# v1.net
KiCad netlist of a schematic drawn in EAGLE
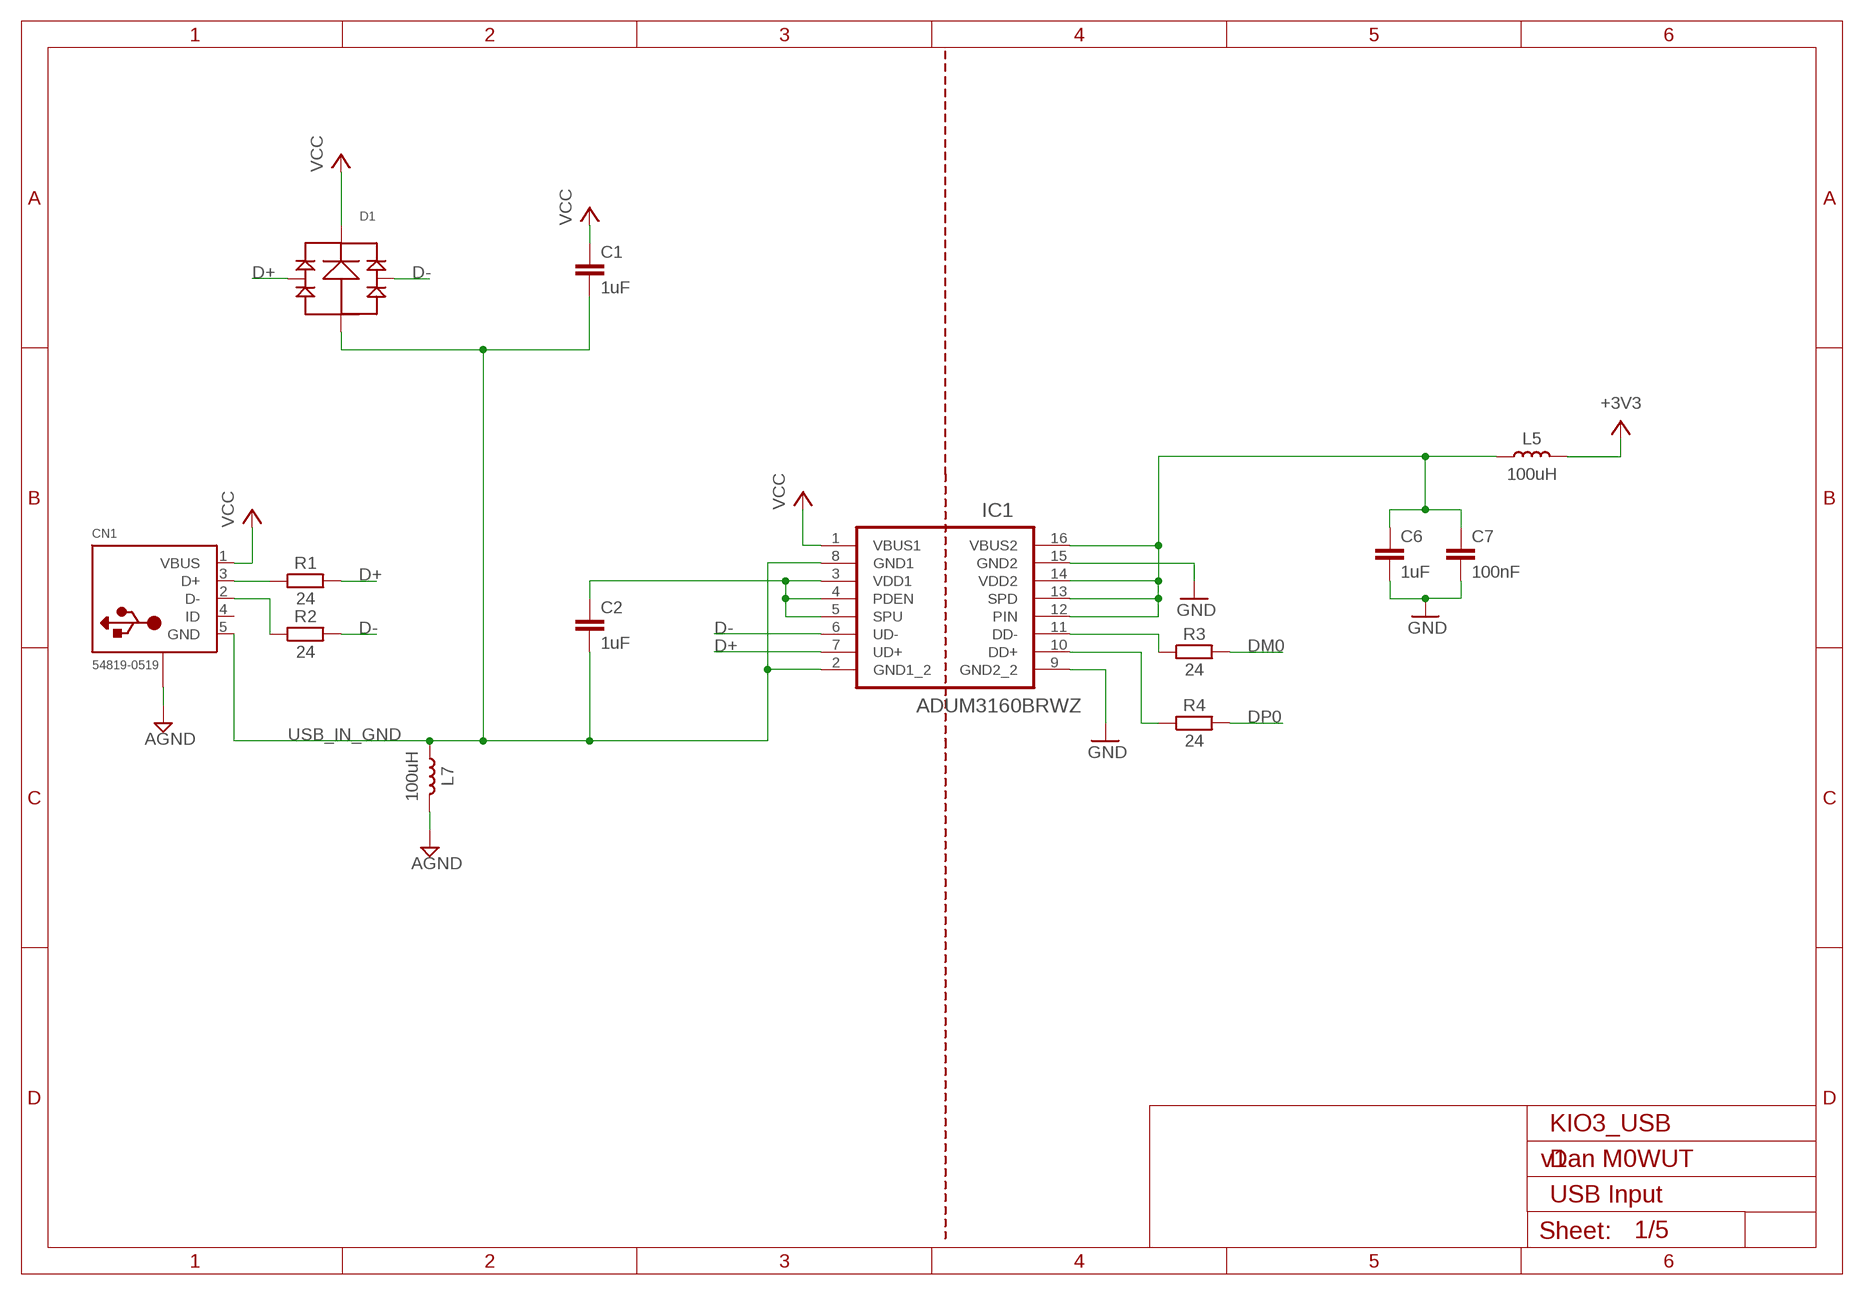
[diagram p0: schematic, sheet 1]
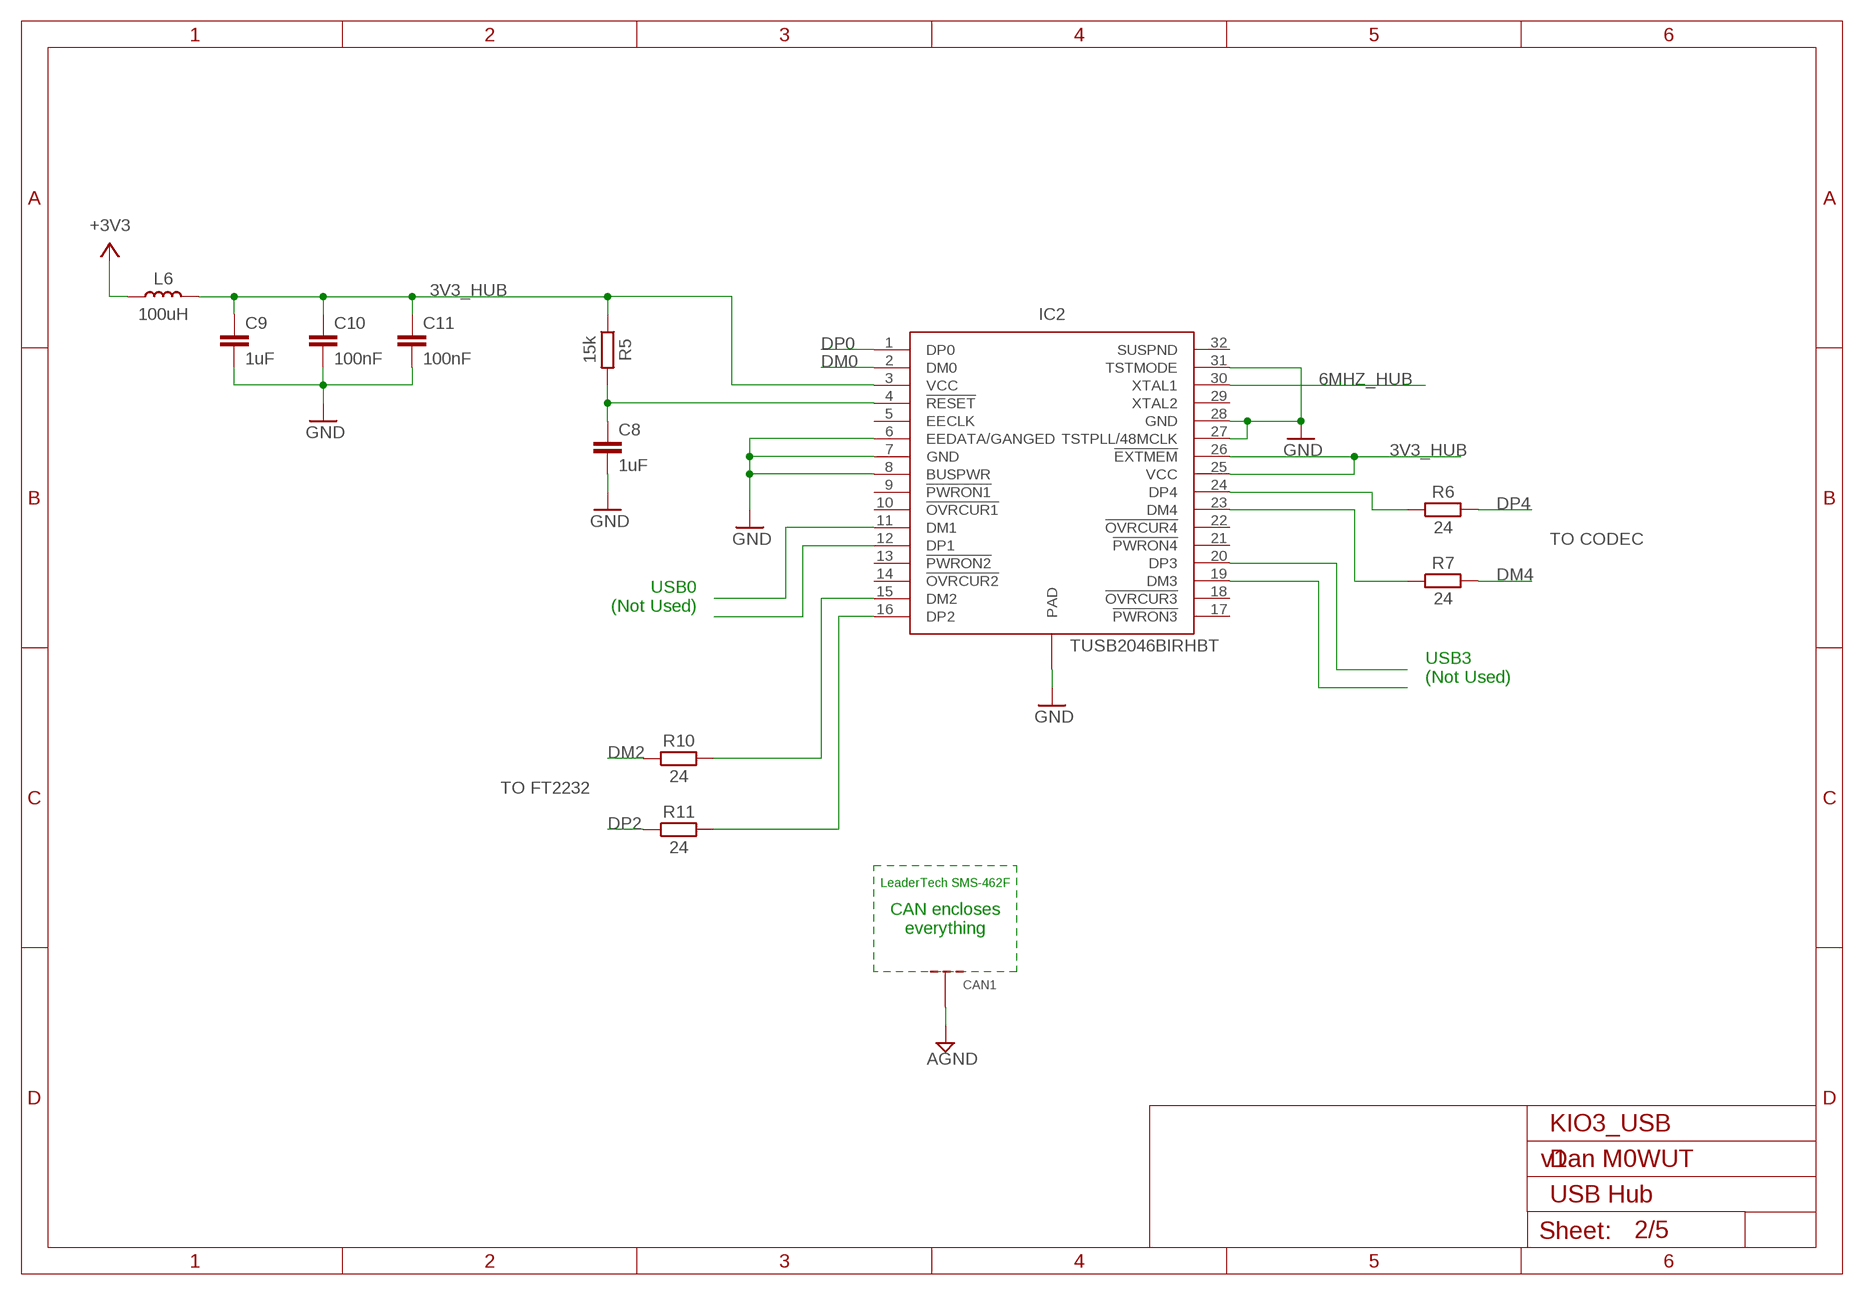
[diagram p1: schematic, sheet 2]
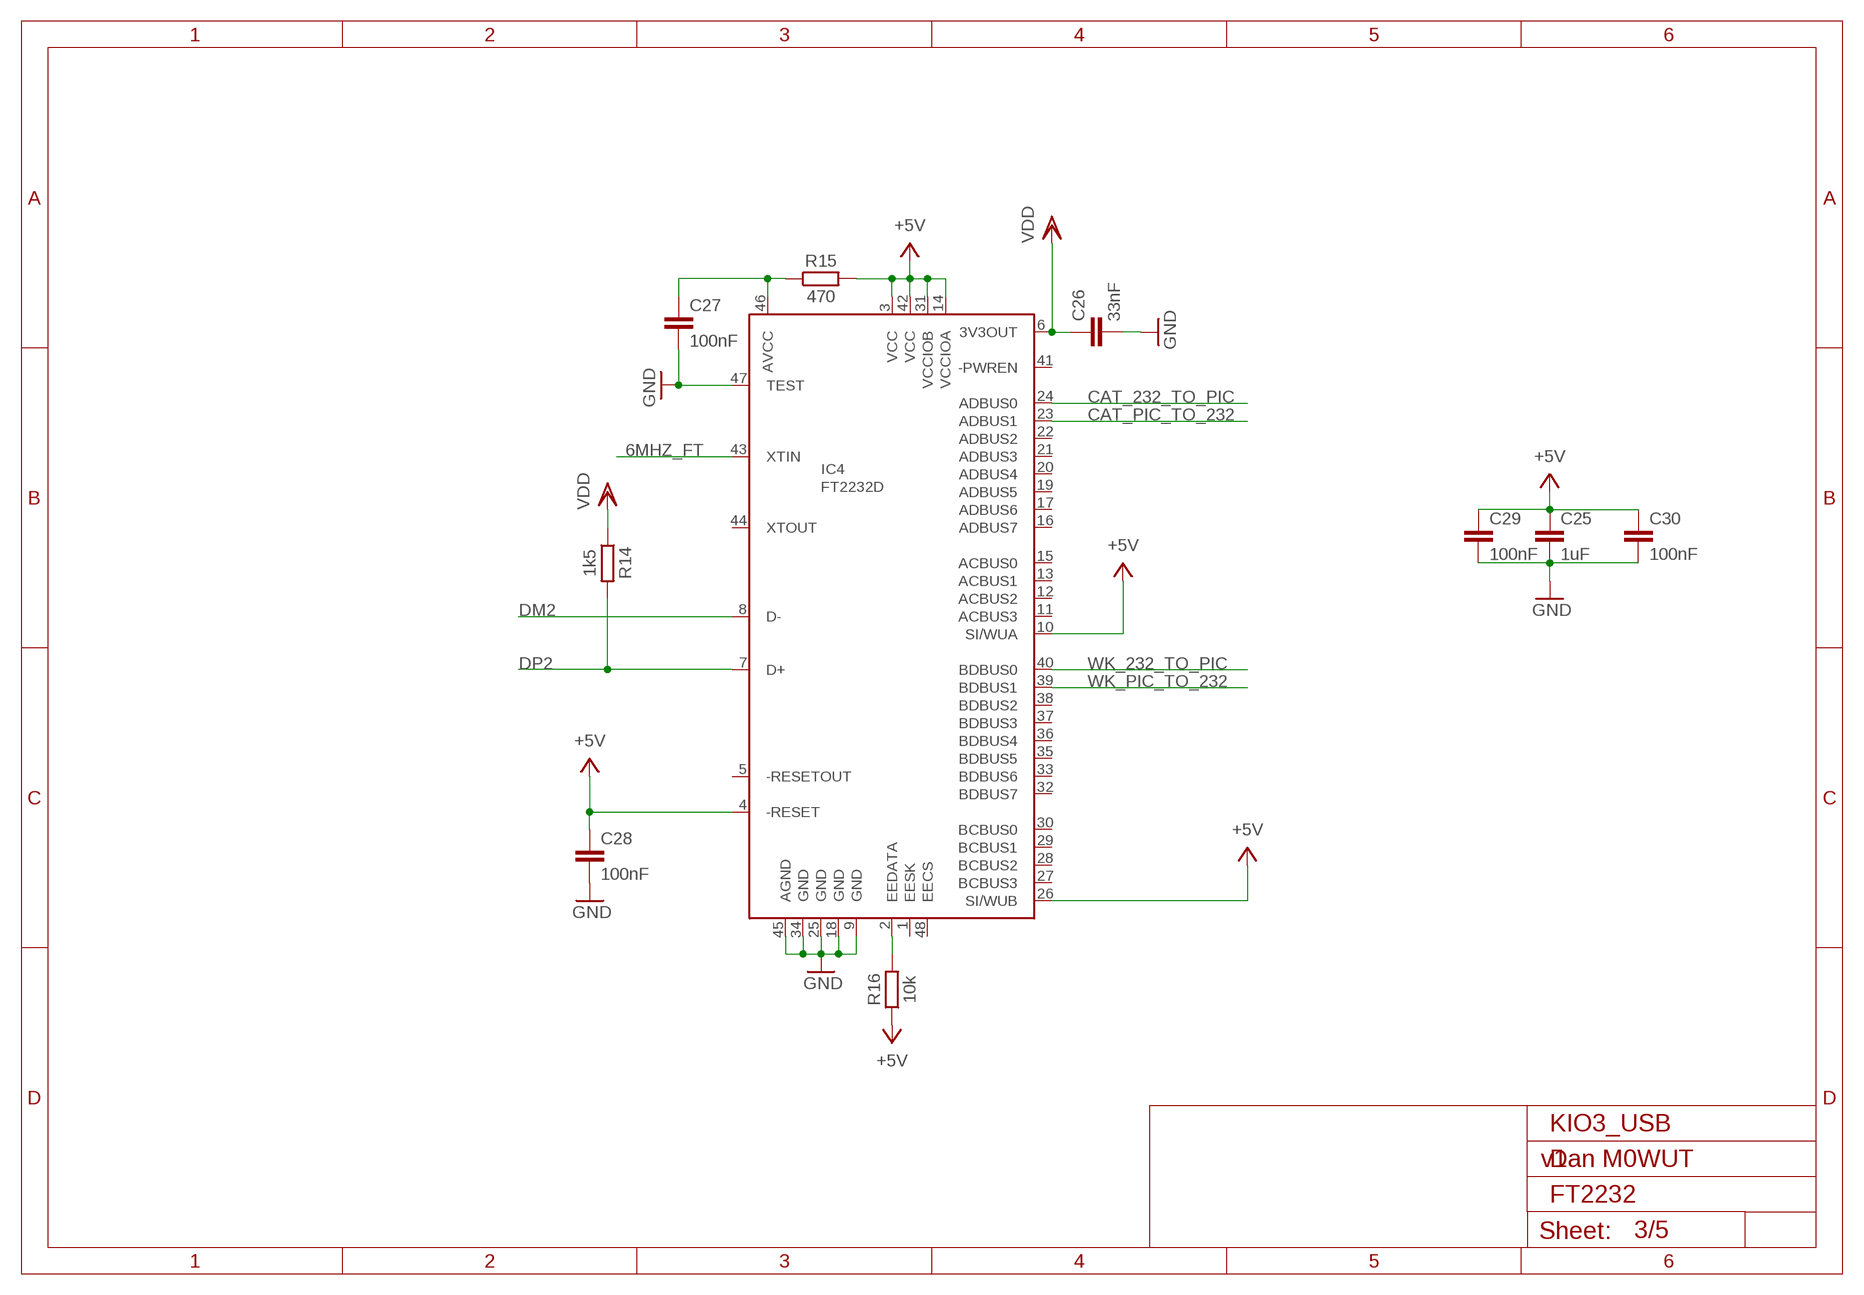
[diagram p2: schematic, sheet 3]
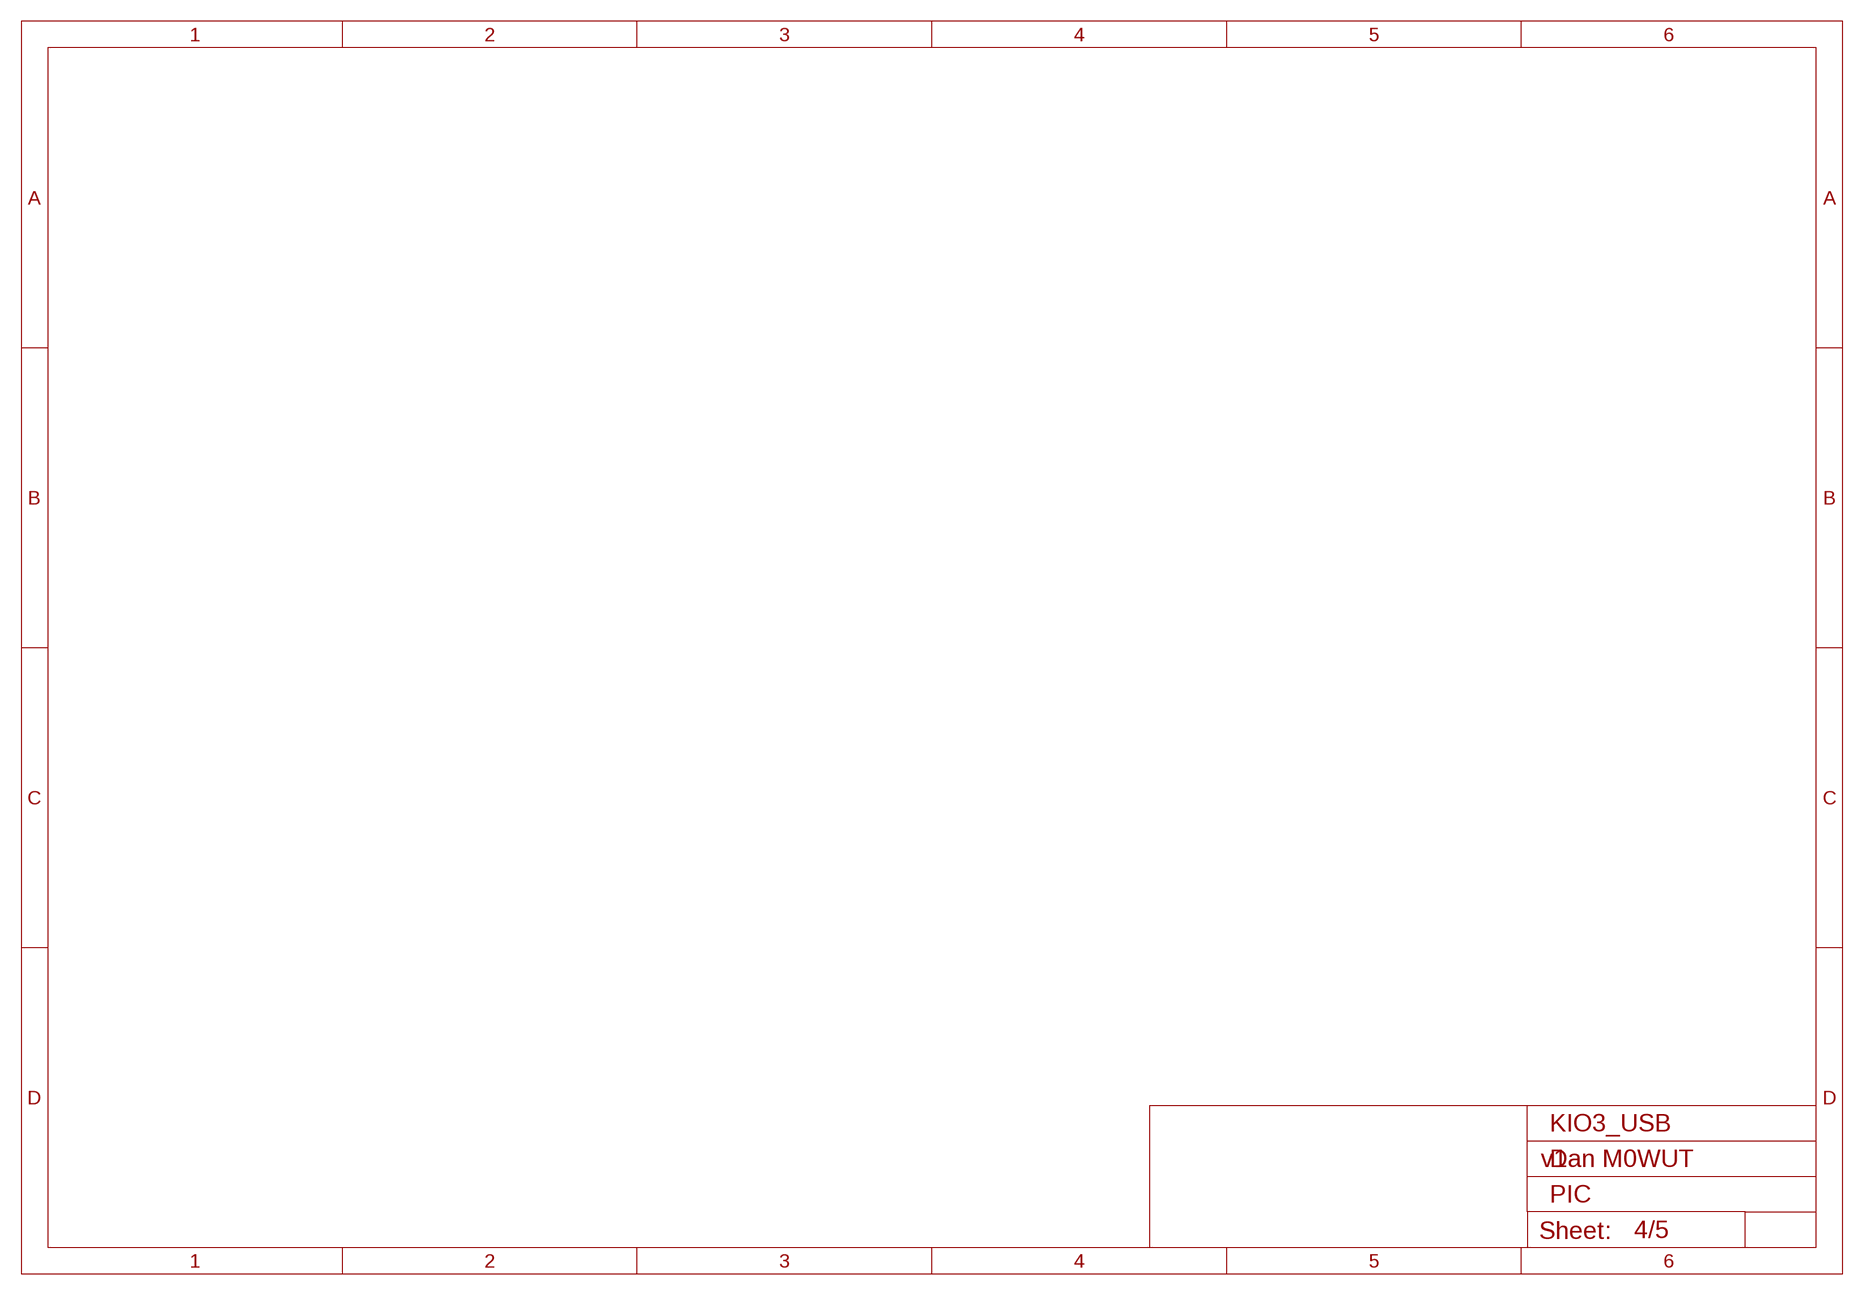
[diagram p3: schematic, sheet 4]
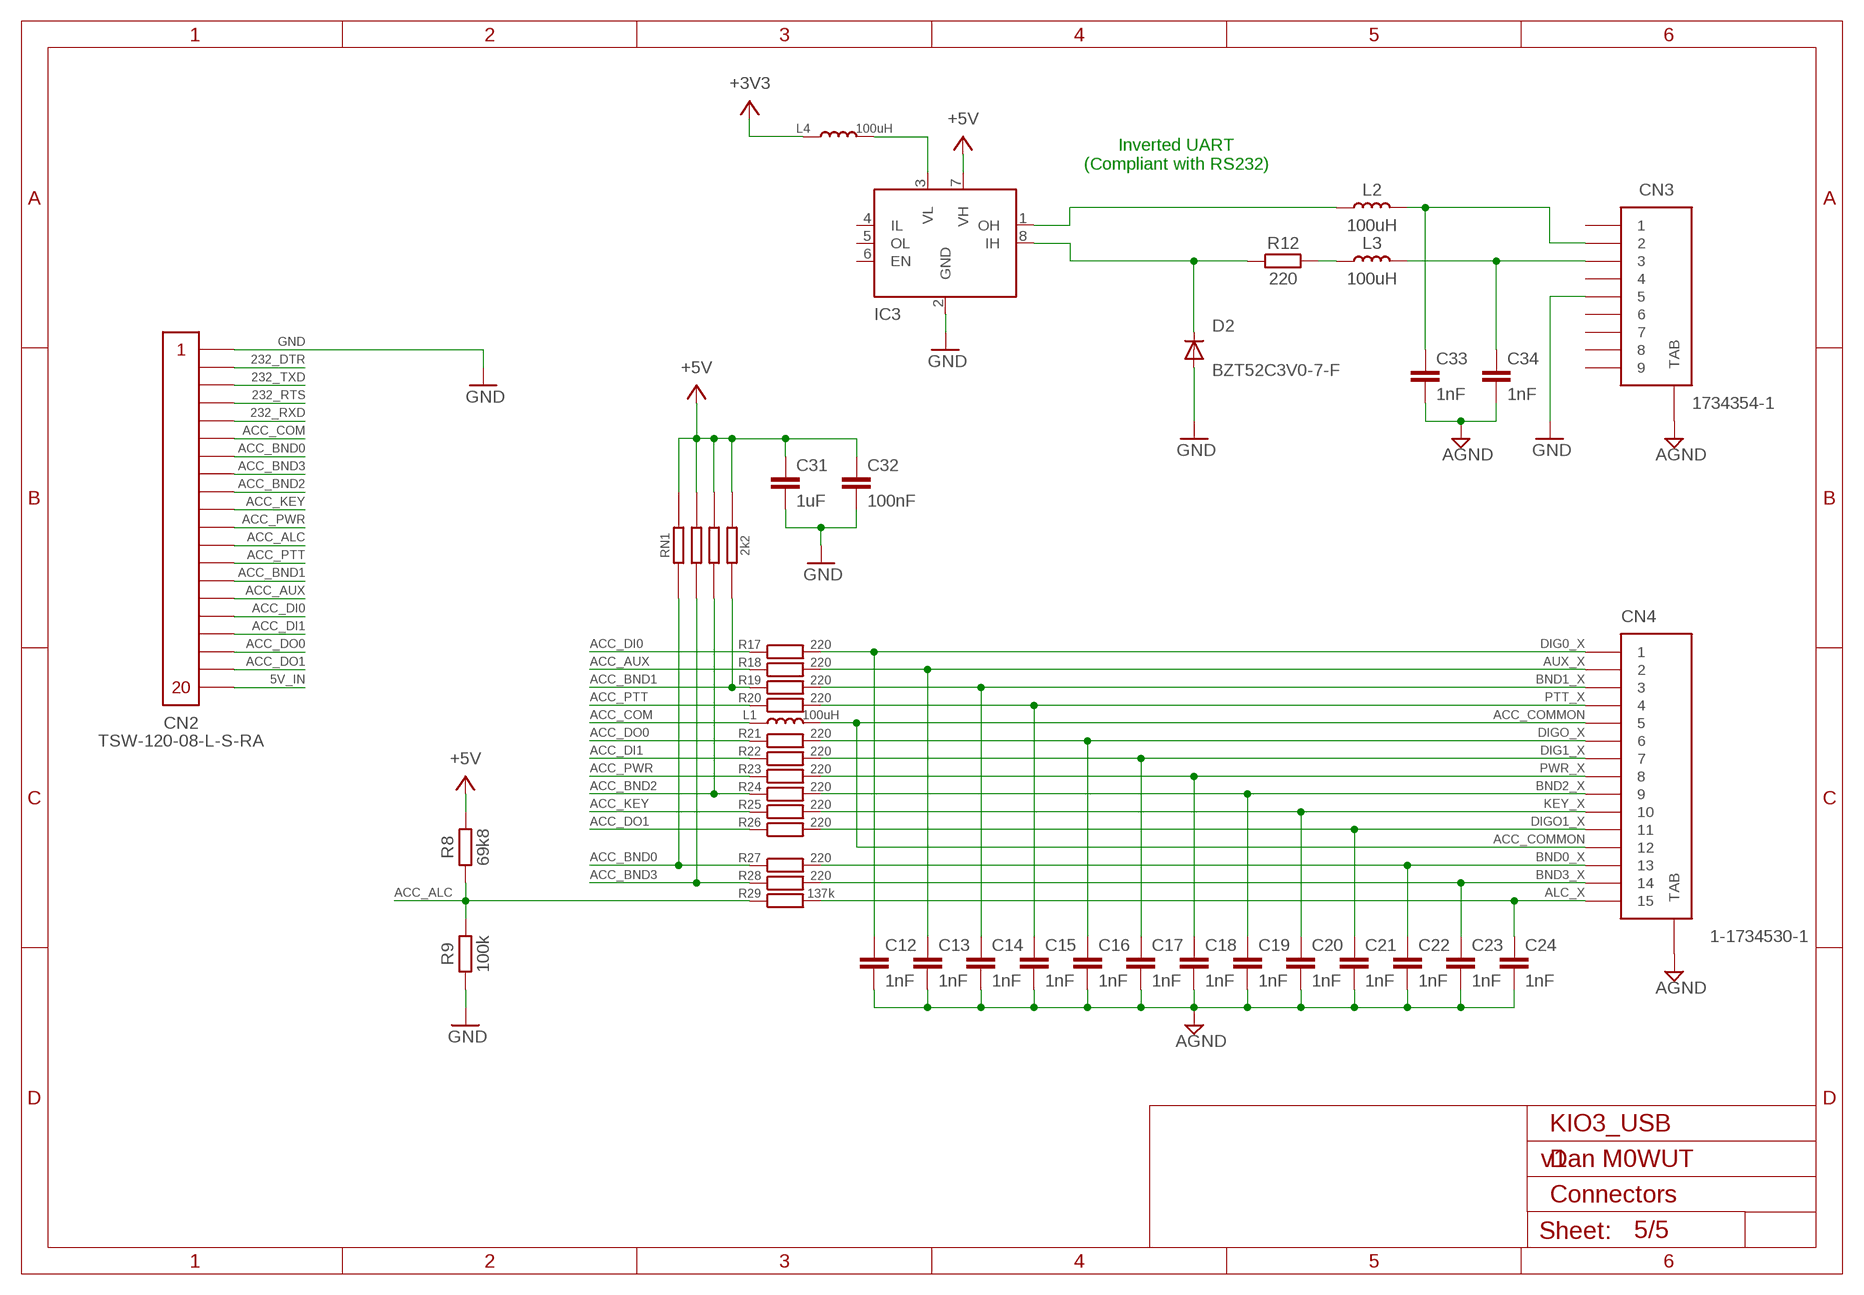
[diagram p4: schematic, sheet 5]

(export (version "E")
  (design (tool "Eeschema 10.0.6"))
  (components
    (comp (ref "C1")
      (value "1uF")
      (footprint "eagle-import:C0402")
      (libsource (lib "eagle-import") (part "C-EUC0402"))
    )
    (comp (ref "C2")
      (value "1uF")
      (footprint "eagle-import:C0402")
      (libsource (lib "eagle-import") (part "C-EUC0402"))
    )
    (comp (ref "C6")
      (value "1uF")
      (footprint "eagle-import:C0402")
      (libsource (lib "eagle-import") (part "C-EUC0402"))
    )
    (comp (ref "C7")
      (value "100nF")
      (footprint "eagle-import:C0402")
      (libsource (lib "eagle-import") (part "C-EUC0402"))
    )
    (comp (ref "CN1")
      (value "54819-0519")
      (footprint "eagle-import:CONN_USB_MOLEX_MINI")
      (libsource (lib "eagle-import") (part "USBMOLEX_MINI"))
    )
    (comp (ref "D1")
      (value "D_ST_USBULC6")
      (footprint "eagle-import:UQFN6")
      (libsource (lib "eagle-import") (part "D_ST_USBULC6"))
    )
    (comp (ref "IC1")
      (value "ADUM3160BRWZ")
      (footprint "eagle-import:SOIC127P1032X265-16N")
      (libsource (lib "eagle-import") (part "ADUM3160BRWZ"))
    )
    (comp (ref "L5")
      (value "100uH")
      (footprint "eagle-import:R0805")
      (libsource (lib "eagle-import") (part "INDUCTOR"))
    )
    (comp (ref "L7")
      (value "100uH")
      (footprint "eagle-import:R0805")
      (libsource (lib "eagle-import") (part "INDUCTOR"))
    )
    (comp (ref "R1")
      (value "24")
      (footprint "eagle-import:R0402")
      (libsource (lib "eagle-import") (part "R-EU_R0402"))
    )
    (comp (ref "R2")
      (value "24")
      (footprint "eagle-import:R0402")
      (libsource (lib "eagle-import") (part "R-EU_R0402"))
    )
    (comp (ref "R3")
      (value "24")
      (footprint "eagle-import:R0402")
      (libsource (lib "eagle-import") (part "R-EU_R0402"))
    )
    (comp (ref "R4")
      (value "24")
      (footprint "eagle-import:R0402")
      (libsource (lib "eagle-import") (part "R-EU_R0402"))
    )
    (comp (ref "C25")
      (value "1uF")
      (footprint "eagle-import:C0402")
      (libsource (lib "eagle-import") (part "C-EUC0402"))
    )
    (comp (ref "C26")
      (value "33nF")
      (footprint "eagle-import:C0402")
      (libsource (lib "eagle-import") (part "C-EUC0402"))
    )
    (comp (ref "C27")
      (value "100nF")
      (footprint "eagle-import:C0402")
      (libsource (lib "eagle-import") (part "C-EUC0402"))
    )
    (comp (ref "C28")
      (value "100nF")
      (footprint "eagle-import:C0402")
      (libsource (lib "eagle-import") (part "C-EUC0402"))
    )
    (comp (ref "C29")
      (value "100nF")
      (footprint "eagle-import:C0402")
      (libsource (lib "eagle-import") (part "C-EUC0402"))
    )
    (comp (ref "C30")
      (value "100nF")
      (footprint "eagle-import:C0402")
      (libsource (lib "eagle-import") (part "C-EUC0402"))
    )
    (comp (ref "IC4")
      (value "FT2232D")
      (footprint "eagle-import:QFP48-7X7")
      (libsource (lib "eagle-import") (part "FT2232D"))
    )
    (comp (ref "R14")
      (value "1k5")
      (footprint "eagle-import:R0402")
      (libsource (lib "eagle-import") (part "R-EU_R0402"))
    )
    (comp (ref "R15")
      (value "470")
      (footprint "eagle-import:R0402")
      (libsource (lib "eagle-import") (part "R-EU_R0402"))
    )
    (comp (ref "R16")
      (value "10k")
      (footprint "eagle-import:R0402")
      (libsource (lib "eagle-import") (part "R-EU_R0402"))
    )
    (comp (ref "C8")
      (value "1uF")
      (footprint "eagle-import:C0402")
      (libsource (lib "eagle-import") (part "C-EUC0402"))
    )
    (comp (ref "C9")
      (value "1uF")
      (footprint "eagle-import:C0402")
      (libsource (lib "eagle-import") (part "C-EUC0402"))
    )
    (comp (ref "C10")
      (value "100nF")
      (footprint "eagle-import:C0402")
      (libsource (lib "eagle-import") (part "C-EUC0402"))
    )
    (comp (ref "C11")
      (value "100nF")
      (footprint "eagle-import:C0402")
      (libsource (lib "eagle-import") (part "C-EUC0402"))
    )
    (comp (ref "CAN1")
      (value "SHIELDING_CAN")
      (footprint "eagle-import:CAN_LEADER_SMS462")
      (libsource (lib "eagle-import") (part "SHIELDING_CAN"))
    )
    (comp (ref "IC2")
      (value "TUSB2046BIRHBT")
      (footprint "eagle-import:RHB_S-PQFP-N32")
      (libsource (lib "eagle-import") (part "TUSB2046BIRHBIRHB"))
    )
    (comp (ref "L6")
      (value "100uH")
      (footprint "eagle-import:R0805")
      (libsource (lib "eagle-import") (part "INDUCTOR"))
    )
    (comp (ref "R5")
      (value "15k")
      (footprint "eagle-import:R0402")
      (libsource (lib "eagle-import") (part "R-EU_R0402"))
    )
    (comp (ref "R6")
      (value "24")
      (footprint "eagle-import:R0402")
      (libsource (lib "eagle-import") (part "R-EU_R0402"))
    )
    (comp (ref "R7")
      (value "24")
      (footprint "eagle-import:R0402")
      (libsource (lib "eagle-import") (part "R-EU_R0402"))
    )
    (comp (ref "R10")
      (value "24")
      (footprint "eagle-import:R0402")
      (libsource (lib "eagle-import") (part "R-EU_R0402"))
    )
    (comp (ref "R11")
      (value "24")
      (footprint "eagle-import:R0402")
      (libsource (lib "eagle-import") (part "R-EU_R0402"))
    )
    (comp (ref "C12")
      (value "1nF")
      (footprint "eagle-import:C0402")
      (libsource (lib "eagle-import") (part "C-EUC0402"))
    )
    (comp (ref "C13")
      (value "1nF")
      (footprint "eagle-import:C0402")
      (libsource (lib "eagle-import") (part "C-EUC0402"))
    )
    (comp (ref "C14")
      (value "1nF")
      (footprint "eagle-import:C0402")
      (libsource (lib "eagle-import") (part "C-EUC0402"))
    )
    (comp (ref "C15")
      (value "1nF")
      (footprint "eagle-import:C0402")
      (libsource (lib "eagle-import") (part "C-EUC0402"))
    )
    (comp (ref "C16")
      (value "1nF")
      (footprint "eagle-import:C0402")
      (libsource (lib "eagle-import") (part "C-EUC0402"))
    )
    (comp (ref "C17")
      (value "1nF")
      (footprint "eagle-import:C0402")
      (libsource (lib "eagle-import") (part "C-EUC0402"))
    )
    (comp (ref "C18")
      (value "1nF")
      (footprint "eagle-import:C0402")
      (libsource (lib "eagle-import") (part "C-EUC0402"))
    )
    (comp (ref "C19")
      (value "1nF")
      (footprint "eagle-import:C0402")
      (libsource (lib "eagle-import") (part "C-EUC0402"))
    )
    (comp (ref "C20")
      (value "1nF")
      (footprint "eagle-import:C0402")
      (libsource (lib "eagle-import") (part "C-EUC0402"))
    )
    (comp (ref "C21")
      (value "1nF")
      (footprint "eagle-import:C0402")
      (libsource (lib "eagle-import") (part "C-EUC0402"))
    )
    (comp (ref "C22")
      (value "1nF")
      (footprint "eagle-import:C0402")
      (libsource (lib "eagle-import") (part "C-EUC0402"))
    )
    (comp (ref "C23")
      (value "1nF")
      (footprint "eagle-import:C0402")
      (libsource (lib "eagle-import") (part "C-EUC0402"))
    )
    (comp (ref "C24")
      (value "1nF")
      (footprint "eagle-import:C0402")
      (libsource (lib "eagle-import") (part "C-EUC0402"))
    )
    (comp (ref "C31")
      (value "1uF")
      (footprint "eagle-import:C0402")
      (libsource (lib "eagle-import") (part "C-EUC0402"))
    )
    (comp (ref "C32")
      (value "100nF")
      (footprint "eagle-import:C0402")
      (libsource (lib "eagle-import") (part "C-EUC0402"))
    )
    (comp (ref "C33")
      (value "1nF")
      (footprint "eagle-import:C0402")
      (libsource (lib "eagle-import") (part "C-EUC0402"))
    )
    (comp (ref "C34")
      (value "1nF")
      (footprint "eagle-import:C0402")
      (libsource (lib "eagle-import") (part "C-EUC0402"))
    )
    (comp (ref "CN2")
      (value "TSW-120-08-L-S-RA")
      (footprint "eagle-import:CONN_0.1_1X20")
      (libsource (lib "eagle-import") (part "CONN_0.1{dblquote}_1X20"))
    )
    (comp (ref "CN3")
      (value "1734354-1")
      (footprint "eagle-import:CONN_TE_DE9")
      (libsource (lib "eagle-import") (part "CONN_TE_DB9"))
    )
    (comp (ref "CN4")
      (value "1-1734530-1")
      (footprint "eagle-import:CONN_TE_DE-HD15")
      (libsource (lib "eagle-import") (part "CONN_TE_DB-HD15"))
    )
    (comp (ref "D2")
      (value "BZT52C3V0-7-F")
      (footprint "eagle-import:SOD-123")
      (libsource (lib "eagle-import") (part "DIODESOD-123"))
    )
    (comp (ref "IC3")
      (value "IC_MAX3375")
      (footprint "eagle-import:SOT23-8L")
      (libsource (lib "eagle-import") (part "IC_MAX3375"))
    )
    (comp (ref "L1")
      (value "100uH")
      (footprint "eagle-import:R0805")
      (libsource (lib "eagle-import") (part "INDUCTOR"))
    )
    (comp (ref "L2")
      (value "100uH")
      (footprint "eagle-import:R0805")
      (libsource (lib "eagle-import") (part "INDUCTOR"))
    )
    (comp (ref "L3")
      (value "100uH")
      (footprint "eagle-import:R0805")
      (libsource (lib "eagle-import") (part "INDUCTOR"))
    )
    (comp (ref "L4")
      (value "100uH")
      (footprint "eagle-import:R0805")
      (libsource (lib "eagle-import") (part "INDUCTOR"))
    )
    (comp (ref "R8")
      (value "69k8")
      (footprint "eagle-import:R0402")
      (libsource (lib "eagle-import") (part "R-EU_R0402"))
    )
    (comp (ref "R9")
      (value "100k")
      (footprint "eagle-import:R0402")
      (libsource (lib "eagle-import") (part "R-EU_R0402"))
    )
    (comp (ref "R12")
      (value "220")
      (footprint "eagle-import:R0402")
      (libsource (lib "eagle-import") (part "R-EU_R0402"))
    )
    (comp (ref "R17")
      (value "220")
      (footprint "eagle-import:R0805")
      (libsource (lib "eagle-import") (part "R-EU_R0805"))
    )
    (comp (ref "R18")
      (value "220")
      (footprint "eagle-import:R0805")
      (libsource (lib "eagle-import") (part "R-EU_R0805"))
    )
    (comp (ref "R19")
      (value "220")
      (footprint "eagle-import:R0805")
      (libsource (lib "eagle-import") (part "R-EU_R0805"))
    )
    (comp (ref "R20")
      (value "220")
      (footprint "eagle-import:R0805")
      (libsource (lib "eagle-import") (part "R-EU_R0805"))
    )
    (comp (ref "R21")
      (value "220")
      (footprint "eagle-import:R0805")
      (libsource (lib "eagle-import") (part "R-EU_R0805"))
    )
    (comp (ref "R22")
      (value "220")
      (footprint "eagle-import:R0805")
      (libsource (lib "eagle-import") (part "R-EU_R0805"))
    )
    (comp (ref "R23")
      (value "220")
      (footprint "eagle-import:R0805")
      (libsource (lib "eagle-import") (part "R-EU_R0805"))
    )
    (comp (ref "R24")
      (value "220")
      (footprint "eagle-import:R0805")
      (libsource (lib "eagle-import") (part "R-EU_R0805"))
    )
    (comp (ref "R25")
      (value "220")
      (footprint "eagle-import:R0805")
      (libsource (lib "eagle-import") (part "R-EU_R0805"))
    )
    (comp (ref "R26")
      (value "220")
      (footprint "eagle-import:R0805")
      (libsource (lib "eagle-import") (part "R-EU_R0805"))
    )
    (comp (ref "R27")
      (value "220")
      (footprint "eagle-import:R0805")
      (libsource (lib "eagle-import") (part "R-EU_R0805"))
    )
    (comp (ref "R28")
      (value "220")
      (footprint "eagle-import:R0805")
      (libsource (lib "eagle-import") (part "R-EU_R0805"))
    )
    (comp (ref "R29")
      (value "137k")
      (footprint "eagle-import:R0805")
      (libsource (lib "eagle-import") (part "R-EU_R0805"))
    )
    (comp (ref "RN1")
      (value "2k2")
      (footprint "eagle-import:R_BOURNS_CAY16-J4")
      (libsource (lib "eagle-import") (part "R_BOURNS_CAY16-J4"))
    )
  )
  (nets
    (net (code "1") (name "+3V3") (class "Default")
      (node (ref "L4") (pin "1") (pinfunction "1_1") (pintype "bidirectional"))
      (node (ref "L5") (pin "2") (pinfunction "2_2") (pintype "bidirectional"))
      (node (ref "L6") (pin "1") (pinfunction "1_1") (pintype "bidirectional"))
    )
    (net (code "2") (name "+5V") (class "Default")
      (node (ref "C25") (pin "1") (pinfunction "1_1") (pintype "passive"))
      (node (ref "C28") (pin "1") (pinfunction "1_1") (pintype "passive"))
      (node (ref "C29") (pin "1") (pinfunction "1_1") (pintype "passive"))
      (node (ref "C30") (pin "1") (pinfunction "1_1") (pintype "passive"))
      (node (ref "C31") (pin "1") (pinfunction "1_1") (pintype "passive"))
      (node (ref "C32") (pin "1") (pinfunction "1_1") (pintype "passive"))
      (node (ref "IC3") (pin "7") (pinfunction "VH_7") (pintype "bidirectional"))
      (node (ref "IC4") (pin "10") (pinfunction "SI/WUA_10") (pintype "bidirectional"))
      (node (ref "IC4") (pin "14") (pinfunction "VCCIOA_14") (pintype "power_in"))
      (node (ref "IC4") (pin "26") (pinfunction "SI/WUB_26") (pintype "bidirectional"))
      (node (ref "IC4") (pin "3") (pinfunction "VCC_3") (pintype "power_in"))
      (node (ref "IC4") (pin "31") (pinfunction "VCCIOB_31") (pintype "power_in"))
      (node (ref "IC4") (pin "4") (pinfunction "-RESET_4") (pintype "input"))
      (node (ref "IC4") (pin "42") (pinfunction "VCC_42") (pintype "power_in"))
      (node (ref "R15") (pin "2") (pinfunction "2_2") (pintype "passive"))
      (node (ref "R16") (pin "1") (pinfunction "1_1") (pintype "passive"))
      (node (ref "R8") (pin "2") (pinfunction "2_2") (pintype "passive"))
      (node (ref "RN1") (pin "1") (pinfunction "1_1") (pintype "bidirectional"))
      (node (ref "RN1") (pin "2") (pinfunction "2_2") (pintype "bidirectional"))
      (node (ref "RN1") (pin "3") (pinfunction "3_3") (pintype "bidirectional"))
      (node (ref "RN1") (pin "4") (pinfunction "4_4") (pintype "bidirectional"))
    )
    (net (code "3") (name "3V3_HUB") (class "Default")
      (node (ref "C10") (pin "1") (pinfunction "1_1") (pintype "passive"))
      (node (ref "C11") (pin "1") (pinfunction "1_1") (pintype "passive"))
      (node (ref "C9") (pin "1") (pinfunction "1_1") (pintype "passive"))
      (node (ref "IC2") (pin "25") (pinfunction "VCC_25") (pintype "power_in"))
      (node (ref "IC2") (pin "26") (pinfunction "~{EXTMEM}_26") (pintype "input"))
      (node (ref "IC2") (pin "3") (pinfunction "VCC_3") (pintype "power_in"))
      (node (ref "L6") (pin "2") (pinfunction "2_2") (pintype "bidirectional"))
      (node (ref "R5") (pin "1") (pinfunction "1_1") (pintype "passive"))
    )
    (net (code "4") (name "5V_IN") (class "Default")
      (node (ref "CN2") (pin "P$20") (pinfunction "P$20_P$20") (pintype "bidirectional"))
    )
    (net (code "5") (name "6MHZ_FT") (class "Default")
      (node (ref "IC4") (pin "43") (pinfunction "XTIN_43") (pintype "input"))
    )
    (net (code "6") (name "6MHZ_HUB") (class "Default")
      (node (ref "IC2") (pin "30") (pinfunction "XTAL1_30") (pintype "input"))
    )
    (net (code "7") (name "232_DTR") (class "Default")
      (node (ref "CN2") (pin "P$2") (pinfunction "P$2_P$2") (pintype "bidirectional"))
    )
    (net (code "8") (name "232_RTS") (class "Default")
      (node (ref "CN2") (pin "P$4") (pinfunction "P$4_P$4") (pintype "bidirectional"))
    )
    (net (code "9") (name "232_RXD") (class "Default")
      (node (ref "CN2") (pin "P$5") (pinfunction "P$5_P$5") (pintype "bidirectional"))
    )
    (net (code "10") (name "232_TXD") (class "Default")
      (node (ref "CN2") (pin "P$3") (pinfunction "P$3_P$3") (pintype "bidirectional"))
    )
    (net (code "11") (name "ACC_ALC") (class "Default")
      (node (ref "CN2") (pin "P$12") (pinfunction "P$12_P$12") (pintype "bidirectional"))
      (node (ref "R29") (pin "1") (pinfunction "1_1") (pintype "passive"))
      (node (ref "R8") (pin "1") (pinfunction "1_1") (pintype "passive"))
      (node (ref "R9") (pin "2") (pinfunction "2_2") (pintype "passive"))
    )
    (net (code "12") (name "ACC_AUX") (class "Default")
      (node (ref "CN2") (pin "P$15") (pinfunction "P$15_P$15") (pintype "bidirectional"))
      (node (ref "R18") (pin "1") (pinfunction "1_1") (pintype "passive"))
    )
    (net (code "13") (name "ACC_BND0") (class "Default")
      (node (ref "CN2") (pin "P$7") (pinfunction "P$7_P$7") (pintype "bidirectional"))
      (node (ref "R27") (pin "1") (pinfunction "1_1") (pintype "passive"))
      (node (ref "RN1") (pin "1A") (pinfunction "1A_1A") (pintype "bidirectional"))
    )
    (net (code "14") (name "ACC_BND1") (class "Default")
      (node (ref "CN2") (pin "P$14") (pinfunction "P$14_P$14") (pintype "bidirectional"))
      (node (ref "R19") (pin "1") (pinfunction "1_1") (pintype "passive"))
      (node (ref "RN1") (pin "4A") (pinfunction "4A_4A") (pintype "bidirectional"))
    )
    (net (code "15") (name "ACC_BND2") (class "Default")
      (node (ref "CN2") (pin "P$9") (pinfunction "P$9_P$9") (pintype "bidirectional"))
      (node (ref "R24") (pin "1") (pinfunction "1_1") (pintype "passive"))
      (node (ref "RN1") (pin "3A") (pinfunction "3A_3A") (pintype "bidirectional"))
    )
    (net (code "16") (name "ACC_BND3") (class "Default")
      (node (ref "CN2") (pin "P$8") (pinfunction "P$8_P$8") (pintype "bidirectional"))
      (node (ref "R28") (pin "1") (pinfunction "1_1") (pintype "passive"))
      (node (ref "RN1") (pin "2A") (pinfunction "2A_2A") (pintype "bidirectional"))
    )
    (net (code "17") (name "ACC_COM") (class "Default")
      (node (ref "CN2") (pin "P$6") (pinfunction "P$6_P$6") (pintype "bidirectional"))
      (node (ref "L1") (pin "1") (pinfunction "1_1") (pintype "bidirectional"))
    )
    (net (code "18") (name "ACC_COMMON") (class "Default")
      (node (ref "CN4") (pin "12") (pinfunction "12_12") (pintype "bidirectional"))
      (node (ref "CN4") (pin "5") (pinfunction "5_5") (pintype "bidirectional"))
      (node (ref "L1") (pin "2") (pinfunction "2_2") (pintype "bidirectional"))
    )
    (net (code "19") (name "ACC_DI0") (class "Default")
      (node (ref "CN2") (pin "P$16") (pinfunction "P$16_P$16") (pintype "bidirectional"))
      (node (ref "R17") (pin "1") (pinfunction "1_1") (pintype "passive"))
    )
    (net (code "20") (name "ACC_DI1") (class "Default")
      (node (ref "CN2") (pin "P$17") (pinfunction "P$17_P$17") (pintype "bidirectional"))
      (node (ref "R22") (pin "1") (pinfunction "1_1") (pintype "passive"))
    )
    (net (code "21") (name "ACC_DO0") (class "Default")
      (node (ref "CN2") (pin "P$18") (pinfunction "P$18_P$18") (pintype "bidirectional"))
      (node (ref "R21") (pin "1") (pinfunction "1_1") (pintype "passive"))
    )
    (net (code "22") (name "ACC_DO1") (class "Default")
      (node (ref "CN2") (pin "P$19") (pinfunction "P$19_P$19") (pintype "bidirectional"))
      (node (ref "R26") (pin "1") (pinfunction "1_1") (pintype "passive"))
    )
    (net (code "23") (name "ACC_KEY") (class "Default")
      (node (ref "CN2") (pin "P$10") (pinfunction "P$10_P$10") (pintype "bidirectional"))
      (node (ref "R25") (pin "1") (pinfunction "1_1") (pintype "passive"))
    )
    (net (code "24") (name "ACC_PTT") (class "Default")
      (node (ref "CN2") (pin "P$13") (pinfunction "P$13_P$13") (pintype "bidirectional"))
      (node (ref "R20") (pin "1") (pinfunction "1_1") (pintype "passive"))
    )
    (net (code "25") (name "ACC_PWR") (class "Default")
      (node (ref "CN2") (pin "P$11") (pinfunction "P$11_P$11") (pintype "bidirectional"))
      (node (ref "R23") (pin "1") (pinfunction "1_1") (pintype "passive"))
    )
    (net (code "26") (name "AGND") (class "Default")
      (node (ref "C12") (pin "2") (pinfunction "2_2") (pintype "passive"))
      (node (ref "C13") (pin "2") (pinfunction "2_2") (pintype "passive"))
      (node (ref "C14") (pin "2") (pinfunction "2_2") (pintype "passive"))
      (node (ref "C15") (pin "2") (pinfunction "2_2") (pintype "passive"))
      (node (ref "C16") (pin "2") (pinfunction "2_2") (pintype "passive"))
      (node (ref "C17") (pin "2") (pinfunction "2_2") (pintype "passive"))
      (node (ref "C18") (pin "2") (pinfunction "2_2") (pintype "passive"))
      (node (ref "C19") (pin "2") (pinfunction "2_2") (pintype "passive"))
      (node (ref "C20") (pin "2") (pinfunction "2_2") (pintype "passive"))
      (node (ref "C21") (pin "2") (pinfunction "2_2") (pintype "passive"))
      (node (ref "C22") (pin "2") (pinfunction "2_2") (pintype "passive"))
      (node (ref "C23") (pin "2") (pinfunction "2_2") (pintype "passive"))
      (node (ref "C24") (pin "2") (pinfunction "2_2") (pintype "passive"))
      (node (ref "C33") (pin "2") (pinfunction "2_2") (pintype "passive"))
      (node (ref "C34") (pin "2") (pinfunction "2_2") (pintype "passive"))
      (node (ref "CAN1") (pin "P$1") (pinfunction "P$1_P$1") (pintype "bidirectional"))
      (node (ref "CAN1") (pin "P$10") (pinfunction "P$1_P$10") (pintype "bidirectional"))
      (node (ref "CAN1") (pin "P$11") (pinfunction "P$1_P$11") (pintype "bidirectional"))
      (node (ref "CAN1") (pin "P$12") (pinfunction "P$1_P$12") (pintype "bidirectional"))
      (node (ref "CAN1") (pin "P$13") (pinfunction "P$1_P$13") (pintype "bidirectional"))
      (node (ref "CAN1") (pin "P$14") (pinfunction "P$1_P$14") (pintype "bidirectional"))
      (node (ref "CAN1") (pin "P$15") (pinfunction "P$1_P$15") (pintype "bidirectional"))
      (node (ref "CAN1") (pin "P$16") (pinfunction "P$1_P$16") (pintype "bidirectional"))
      (node (ref "CAN1") (pin "P$17") (pinfunction "P$1_P$17") (pintype "bidirectional"))
      (node (ref "CAN1") (pin "P$18") (pinfunction "P$1_P$18") (pintype "bidirectional"))
      (node (ref "CAN1") (pin "P$19") (pinfunction "P$1_P$19") (pintype "bidirectional"))
      (node (ref "CAN1") (pin "P$2") (pinfunction "P$1_P$2") (pintype "bidirectional"))
      (node (ref "CAN1") (pin "P$20") (pinfunction "P$1_P$20") (pintype "bidirectional"))
      (node (ref "CAN1") (pin "P$21") (pinfunction "P$1_P$21") (pintype "bidirectional"))
      (node (ref "CAN1") (pin "P$22") (pinfunction "P$1_P$22") (pintype "bidirectional"))
      (node (ref "CAN1") (pin "P$23") (pinfunction "P$1_P$23") (pintype "bidirectional"))
      (node (ref "CAN1") (pin "P$24") (pinfunction "P$1_P$24") (pintype "bidirectional"))
      (node (ref "CAN1") (pin "P$25") (pinfunction "P$1_P$25") (pintype "bidirectional"))
      (node (ref "CAN1") (pin "P$26") (pinfunction "P$1_P$26") (pintype "bidirectional"))
      (node (ref "CAN1") (pin "P$27") (pinfunction "P$1_P$27") (pintype "bidirectional"))
      (node (ref "CAN1") (pin "P$28") (pinfunction "P$1_P$28") (pintype "bidirectional"))
      (node (ref "CAN1") (pin "P$29") (pinfunction "P$1_P$29") (pintype "bidirectional"))
      (node (ref "CAN1") (pin "P$3") (pinfunction "P$1_P$3") (pintype "bidirectional"))
      (node (ref "CAN1") (pin "P$30") (pinfunction "P$1_P$30") (pintype "bidirectional"))
      (node (ref "CAN1") (pin "P$31") (pinfunction "P$1_P$31") (pintype "bidirectional"))
      (node (ref "CAN1") (pin "P$32") (pinfunction "P$1_P$32") (pintype "bidirectional"))
      (node (ref "CAN1") (pin "P$33") (pinfunction "P$1_P$33") (pintype "bidirectional"))
      (node (ref "CAN1") (pin "P$34") (pinfunction "P$1_P$34") (pintype "bidirectional"))
      (node (ref "CAN1") (pin "P$35") (pinfunction "P$1_P$35") (pintype "bidirectional"))
      (node (ref "CAN1") (pin "P$36") (pinfunction "P$1_P$36") (pintype "bidirectional"))
      (node (ref "CAN1") (pin "P$37") (pinfunction "P$1_P$37") (pintype "bidirectional"))
      (node (ref "CAN1") (pin "P$38") (pinfunction "P$1_P$38") (pintype "bidirectional"))
      (node (ref "CAN1") (pin "P$39") (pinfunction "P$1_P$39") (pintype "bidirectional"))
      (node (ref "CAN1") (pin "P$4") (pinfunction "P$1_P$4") (pintype "bidirectional"))
      (node (ref "CAN1") (pin "P$40") (pinfunction "P$1_P$40") (pintype "bidirectional"))
      (node (ref "CAN1") (pin "P$41") (pinfunction "P$1_P$41") (pintype "bidirectional"))
      (node (ref "CAN1") (pin "P$42") (pinfunction "P$1_P$42") (pintype "bidirectional"))
      (node (ref "CAN1") (pin "P$43") (pinfunction "P$1_P$43") (pintype "bidirectional"))
      (node (ref "CAN1") (pin "P$44") (pinfunction "P$1_P$44") (pintype "bidirectional"))
      (node (ref "CAN1") (pin "P$45") (pinfunction "P$1_P$45") (pintype "bidirectional"))
      (node (ref "CAN1") (pin "P$46") (pinfunction "P$1_P$46") (pintype "bidirectional"))
      (node (ref "CAN1") (pin "P$47") (pinfunction "P$1_P$47") (pintype "bidirectional"))
      (node (ref "CAN1") (pin "P$48") (pinfunction "P$1_P$48") (pintype "bidirectional"))
      (node (ref "CAN1") (pin "P$49") (pinfunction "P$1_P$49") (pintype "bidirectional"))
      (node (ref "CAN1") (pin "P$5") (pinfunction "P$1_P$5") (pintype "bidirectional"))
      (node (ref "CAN1") (pin "P$50") (pinfunction "P$1_P$50") (pintype "bidirectional"))
      (node (ref "CAN1") (pin "P$51") (pinfunction "P$1_P$51") (pintype "bidirectional"))
      (node (ref "CAN1") (pin "P$52") (pinfunction "P$1_P$52") (pintype "bidirectional"))
      (node (ref "CAN1") (pin "P$53") (pinfunction "P$1_P$53") (pintype "bidirectional"))
      (node (ref "CAN1") (pin "P$54") (pinfunction "P$1_P$54") (pintype "bidirectional"))
      (node (ref "CAN1") (pin "P$55") (pinfunction "P$1_P$55") (pintype "bidirectional"))
      (node (ref "CAN1") (pin "P$56") (pinfunction "P$1_P$56") (pintype "bidirectional"))
      (node (ref "CAN1") (pin "P$57") (pinfunction "P$1_P$57") (pintype "bidirectional"))
      (node (ref "CAN1") (pin "P$58") (pinfunction "P$1_P$58") (pintype "bidirectional"))
      (node (ref "CAN1") (pin "P$59") (pinfunction "P$1_P$59") (pintype "bidirectional"))
      (node (ref "CAN1") (pin "P$6") (pinfunction "P$1_P$6") (pintype "bidirectional"))
      (node (ref "CAN1") (pin "P$60") (pinfunction "P$1_P$60") (pintype "bidirectional"))
      (node (ref "CAN1") (pin "P$61") (pinfunction "P$1_P$61") (pintype "bidirectional"))
      (node (ref "CAN1") (pin "P$62") (pinfunction "P$1_P$62") (pintype "bidirectional"))
      (node (ref "CAN1") (pin "P$63") (pinfunction "P$1_P$63") (pintype "bidirectional"))
      (node (ref "CAN1") (pin "P$64") (pinfunction "P$1_P$64") (pintype "bidirectional"))
      (node (ref "CAN1") (pin "P$65") (pinfunction "P$1_P$65") (pintype "bidirectional"))
      (node (ref "CAN1") (pin "P$66") (pinfunction "P$1_P$66") (pintype "bidirectional"))
      (node (ref "CAN1") (pin "P$67") (pinfunction "P$1_P$67") (pintype "bidirectional"))
      (node (ref "CAN1") (pin "P$68") (pinfunction "P$1_P$68") (pintype "bidirectional"))
      (node (ref "CAN1") (pin "P$7") (pinfunction "P$1_P$7") (pintype "bidirectional"))
      (node (ref "CAN1") (pin "P$8") (pinfunction "P$1_P$8") (pintype "bidirectional"))
      (node (ref "CAN1") (pin "P$9") (pinfunction "P$1_P$9") (pintype "bidirectional"))
      (node (ref "CN1") (pin "TAB") (pinfunction "SHIELD_TAB") (pintype "bidirectional"))
      (node (ref "CN1") (pin "TAB1") (pinfunction "SHIELD_TAB1") (pintype "bidirectional"))
      (node (ref "CN3") (pin "TAB") (pinfunction "TAB_TAB") (pintype "bidirectional"))
      (node (ref "CN3") (pin "TAB1") (pinfunction "TAB_TAB1") (pintype "bidirectional"))
      (node (ref "CN4") (pin "16") (pinfunction "TAB_16") (pintype "bidirectional"))
      (node (ref "CN4") (pin "17") (pinfunction "TAB_17") (pintype "bidirectional"))
      (node (ref "L7") (pin "2") (pinfunction "2_2") (pintype "bidirectional"))
    )
    (net (code "27") (name "ALC_X") (class "Default")
      (node (ref "C24") (pin "1") (pinfunction "1_1") (pintype "passive"))
      (node (ref "CN4") (pin "15") (pinfunction "15_15") (pintype "bidirectional"))
      (node (ref "R29") (pin "2") (pinfunction "2_2") (pintype "passive"))
    )
    (net (code "28") (name "AUX_X") (class "Default")
      (node (ref "C13") (pin "1") (pinfunction "1_1") (pintype "passive"))
      (node (ref "CN4") (pin "2") (pinfunction "2_2") (pintype "bidirectional"))
      (node (ref "R18") (pin "2") (pinfunction "2_2") (pintype "passive"))
    )
    (net (code "29") (name "BND0_X") (class "Default")
      (node (ref "C22") (pin "1") (pinfunction "1_1") (pintype "passive"))
      (node (ref "CN4") (pin "13") (pinfunction "13_13") (pintype "bidirectional"))
      (node (ref "R27") (pin "2") (pinfunction "2_2") (pintype "passive"))
    )
    (net (code "30") (name "BND1_X") (class "Default")
      (node (ref "C14") (pin "1") (pinfunction "1_1") (pintype "passive"))
      (node (ref "CN4") (pin "3") (pinfunction "3_3") (pintype "bidirectional"))
      (node (ref "R19") (pin "2") (pinfunction "2_2") (pintype "passive"))
    )
    (net (code "31") (name "BND2_X") (class "Default")
      (node (ref "C19") (pin "1") (pinfunction "1_1") (pintype "passive"))
      (node (ref "CN4") (pin "9") (pinfunction "9_9") (pintype "bidirectional"))
      (node (ref "R24") (pin "2") (pinfunction "2_2") (pintype "passive"))
    )
    (net (code "32") (name "BND3_X") (class "Default")
      (node (ref "C23") (pin "1") (pinfunction "1_1") (pintype "passive"))
      (node (ref "CN4") (pin "14") (pinfunction "14_14") (pintype "bidirectional"))
      (node (ref "R28") (pin "2") (pinfunction "2_2") (pintype "passive"))
    )
    (net (code "33") (name "CAT_232_TO_PIC") (class "Default")
      (node (ref "IC4") (pin "24") (pinfunction "ADBUS0_24") (pintype "bidirectional"))
    )
    (net (code "34") (name "CAT_PIC_TO_232") (class "Default")
      (node (ref "IC4") (pin "23") (pinfunction "ADBUS1_23") (pintype "bidirectional"))
    )
    (net (code "35") (name "D+") (class "Default")
      (node (ref "D1") (pin "1") (pinfunction "LEFT_1") (pintype "bidirectional"))
      (node (ref "D1") (pin "6") (pinfunction "LEFT_6") (pintype "bidirectional"))
      (node (ref "IC1") (pin "7") (pinfunction "UD+_7") (pintype "bidirectional"))
      (node (ref "R1") (pin "2") (pinfunction "2_2") (pintype "passive"))
    )
    (net (code "36") (name "D-") (class "Default")
      (node (ref "D1") (pin "3") (pinfunction "RIGHT_3") (pintype "bidirectional"))
      (node (ref "D1") (pin "4") (pinfunction "RIGHT_4") (pintype "bidirectional"))
      (node (ref "IC1") (pin "6") (pinfunction "UD-_6") (pintype "bidirectional"))
      (node (ref "R2") (pin "2") (pinfunction "2_2") (pintype "passive"))
    )
    (net (code "37") (name "DIG0_X") (class "Default")
      (node (ref "C12") (pin "1") (pinfunction "1_1") (pintype "passive"))
      (node (ref "CN4") (pin "1") (pinfunction "1_1") (pintype "bidirectional"))
      (node (ref "R17") (pin "2") (pinfunction "2_2") (pintype "passive"))
    )
    (net (code "38") (name "DIG1_X") (class "Default")
      (node (ref "C17") (pin "1") (pinfunction "1_1") (pintype "passive"))
      (node (ref "CN4") (pin "7") (pinfunction "7_7") (pintype "bidirectional"))
      (node (ref "R22") (pin "2") (pinfunction "2_2") (pintype "passive"))
    )
    (net (code "39") (name "DIGO1_X") (class "Default")
      (node (ref "C21") (pin "1") (pinfunction "1_1") (pintype "passive"))
      (node (ref "CN4") (pin "11") (pinfunction "11_11") (pintype "bidirectional"))
      (node (ref "R26") (pin "2") (pinfunction "2_2") (pintype "passive"))
    )
    (net (code "40") (name "DIGO_X") (class "Default")
      (node (ref "C16") (pin "1") (pinfunction "1_1") (pintype "passive"))
      (node (ref "CN4") (pin "6") (pinfunction "6_6") (pintype "bidirectional"))
      (node (ref "R21") (pin "2") (pinfunction "2_2") (pintype "passive"))
    )
    (net (code "41") (name "DM0") (class "Default")
      (node (ref "IC2") (pin "2") (pinfunction "DM0_2") (pintype "bidirectional"))
      (node (ref "R3") (pin "2") (pinfunction "2_2") (pintype "passive"))
    )
    (net (code "42") (name "DM2") (class "Default")
      (node (ref "IC4") (pin "8") (pinfunction "D-_8") (pintype "bidirectional"))
      (node (ref "R10") (pin "1") (pinfunction "1_1") (pintype "passive"))
    )
    (net (code "43") (name "DM4") (class "Default")
      (node (ref "R7") (pin "2") (pinfunction "2_2") (pintype "passive"))
    )
    (net (code "44") (name "DP0") (class "Default")
      (node (ref "IC2") (pin "1") (pinfunction "DP0_1") (pintype "bidirectional"))
      (node (ref "R4") (pin "2") (pinfunction "2_2") (pintype "passive"))
    )
    (net (code "45") (name "DP2") (class "Default")
      (node (ref "IC4") (pin "7") (pinfunction "D+_7") (pintype "bidirectional"))
      (node (ref "R11") (pin "1") (pinfunction "1_1") (pintype "passive"))
      (node (ref "R14") (pin "2") (pinfunction "2_2") (pintype "passive"))
    )
    (net (code "46") (name "DP4") (class "Default")
      (node (ref "R6") (pin "2") (pinfunction "2_2") (pintype "passive"))
    )
    (net (code "47") (name "GND") (class "Default")
      (node (ref "C10") (pin "2") (pinfunction "2_2") (pintype "passive"))
      (node (ref "C11") (pin "2") (pinfunction "2_2") (pintype "passive"))
      (node (ref "C25") (pin "2") (pinfunction "2_2") (pintype "passive"))
      (node (ref "C26") (pin "2") (pinfunction "2_2") (pintype "passive"))
      (node (ref "C27") (pin "2") (pinfunction "2_2") (pintype "passive"))
      (node (ref "C28") (pin "2") (pinfunction "2_2") (pintype "passive"))
      (node (ref "C29") (pin "2") (pinfunction "2_2") (pintype "passive"))
      (node (ref "C30") (pin "2") (pinfunction "2_2") (pintype "passive"))
      (node (ref "C31") (pin "2") (pinfunction "2_2") (pintype "passive"))
      (node (ref "C32") (pin "2") (pinfunction "2_2") (pintype "passive"))
      (node (ref "C6") (pin "2") (pinfunction "2_2") (pintype "passive"))
      (node (ref "C7") (pin "2") (pinfunction "2_2") (pintype "passive"))
      (node (ref "C8") (pin "2") (pinfunction "2_2") (pintype "passive"))
      (node (ref "C9") (pin "2") (pinfunction "2_2") (pintype "passive"))
      (node (ref "CN2") (pin "P$1") (pinfunction "P$1_P$1") (pintype "bidirectional"))
      (node (ref "CN3") (pin "5") (pinfunction "5_5") (pintype "bidirectional"))
      (node (ref "D2") (pin "A") (pinfunction "A_A") (pintype "passive"))
      (node (ref "IC1") (pin "15") (pinfunction "GND2_15") (pintype "passive"))
      (node (ref "IC1") (pin "9") (pinfunction "GND2_2_9") (pintype "passive"))
      (node (ref "IC2") (pin "27") (pinfunction "TSTPLL/48MCLK_27") (pintype "bidirectional"))
      (node (ref "IC2") (pin "28") (pinfunction "GND_28") (pintype "power_in"))
      (node (ref "IC2") (pin "31") (pinfunction "TSTMODE_31") (pintype "input"))
      (node (ref "IC2") (pin "6") (pinfunction "EEDATA/GANGED_6") (pintype "bidirectional"))
      (node (ref "IC2") (pin "7") (pinfunction "GND_7") (pintype "power_in"))
      (node (ref "IC2") (pin "8") (pinfunction "BUSPWR_8") (pintype "input"))
      (node (ref "IC2") (pin "EXP") (pinfunction "PAD_EXP") (pintype "power_in"))
      (node (ref "IC3") (pin "2") (pinfunction "GND_2") (pintype "bidirectional"))
      (node (ref "IC4") (pin "18") (pinfunction "GND_18") (pintype "power_in"))
      (node (ref "IC4") (pin "25") (pinfunction "GND_25") (pintype "power_in"))
      (node (ref "IC4") (pin "34") (pinfunction "GND_34") (pintype "power_in"))
      (node (ref "IC4") (pin "45") (pinfunction "AGND_45") (pintype "power_in"))
      (node (ref "IC4") (pin "47") (pinfunction "TEST_47") (pintype "input"))
      (node (ref "IC4") (pin "9") (pinfunction "GND_9") (pintype "power_in"))
      (node (ref "R9") (pin "1") (pinfunction "1_1") (pintype "passive"))
    )
    (net (code "48") (name "KEY_X") (class "Default")
      (node (ref "C20") (pin "1") (pinfunction "1_1") (pintype "passive"))
      (node (ref "CN4") (pin "10") (pinfunction "10_10") (pintype "bidirectional"))
      (node (ref "R25") (pin "2") (pinfunction "2_2") (pintype "passive"))
    )
    (net (code "49") (name "Net-(C33-Pad1)") (class "Default")
      (node (ref "C33") (pin "1") (pinfunction "1_1") (pintype "passive"))
      (node (ref "CN3") (pin "2") (pinfunction "2_2") (pintype "bidirectional"))
      (node (ref "L2") (pin "2") (pinfunction "2_2") (pintype "bidirectional"))
    )
    (net (code "50") (name "Net-(C34-Pad1)") (class "Default")
      (node (ref "C34") (pin "1") (pinfunction "1_1") (pintype "passive"))
      (node (ref "CN3") (pin "3") (pinfunction "3_3") (pintype "bidirectional"))
      (node (ref "L3") (pin "2") (pinfunction "2_2") (pintype "bidirectional"))
    )
    (net (code "51") (name "Net-(CN1-D+)") (class "Default")
      (node (ref "CN1") (pin "3") (pinfunction "D+_3") (pintype "bidirectional"))
      (node (ref "R1") (pin "1") (pinfunction "1_1") (pintype "passive"))
    )
    (net (code "52") (name "Net-(CN1-D-)") (class "Default")
      (node (ref "CN1") (pin "2") (pinfunction "D-_2") (pintype "bidirectional"))
      (node (ref "R2") (pin "1") (pinfunction "1_1") (pintype "passive"))
    )
    (net (code "53") (name "Net-(IC1-DD+)") (class "Default")
      (node (ref "IC1") (pin "10") (pinfunction "DD+_10") (pintype "bidirectional"))
      (node (ref "R4") (pin "1") (pinfunction "1_1") (pintype "passive"))
    )
    (net (code "54") (name "Net-(IC1-DD-)") (class "Default")
      (node (ref "IC1") (pin "11") (pinfunction "DD-_11") (pintype "bidirectional"))
      (node (ref "R3") (pin "1") (pinfunction "1_1") (pintype "passive"))
    )
    (net (code "55") (name "Net-(IC1-PDEN)") (class "Default")
      (node (ref "C2") (pin "1") (pinfunction "1_1") (pintype "passive"))
      (node (ref "IC1") (pin "3") (pinfunction "VDD1_3") (pintype "power_in"))
      (node (ref "IC1") (pin "4") (pinfunction "PDEN_4") (pintype "input"))
      (node (ref "IC1") (pin "5") (pinfunction "SPU_5") (pintype "input"))
    )
    (net (code "56") (name "Net-(IC1-PIN)") (class "Default")
      (node (ref "C6") (pin "1") (pinfunction "1_1") (pintype "passive"))
      (node (ref "C7") (pin "1") (pinfunction "1_1") (pintype "passive"))
      (node (ref "IC1") (pin "12") (pinfunction "PIN_12") (pintype "input"))
      (node (ref "IC1") (pin "13") (pinfunction "SPD_13") (pintype "input"))
      (node (ref "IC1") (pin "14") (pinfunction "VDD2_14") (pintype "power_in"))
      (node (ref "IC1") (pin "16") (pinfunction "VBUS2_16") (pintype "power_in"))
      (node (ref "L5") (pin "1") (pinfunction "1_1") (pintype "bidirectional"))
    )
    (net (code "57") (name "Net-(IC2-DM2)") (class "Default")
      (node (ref "IC2") (pin "15") (pinfunction "DM2_15") (pintype "bidirectional"))
      (node (ref "R10") (pin "2") (pinfunction "2_2") (pintype "passive"))
    )
    (net (code "58") (name "Net-(IC2-DM4)") (class "Default")
      (node (ref "IC2") (pin "23") (pinfunction "DM4_23") (pintype "bidirectional"))
      (node (ref "R7") (pin "1") (pinfunction "1_1") (pintype "passive"))
    )
    (net (code "59") (name "Net-(IC2-DP2)") (class "Default")
      (node (ref "IC2") (pin "16") (pinfunction "DP2_16") (pintype "bidirectional"))
      (node (ref "R11") (pin "2") (pinfunction "2_2") (pintype "passive"))
    )
    (net (code "60") (name "Net-(IC2-DP4)") (class "Default")
      (node (ref "IC2") (pin "24") (pinfunction "DP4_24") (pintype "bidirectional"))
      (node (ref "R6") (pin "1") (pinfunction "1_1") (pintype "passive"))
    )
    (net (code "61") (name "Net-(IC2-~{RESET})") (class "Default")
      (node (ref "C8") (pin "1") (pinfunction "1_1") (pintype "passive"))
      (node (ref "IC2") (pin "4") (pinfunction "~{RESET}_4") (pintype "input"))
      (node (ref "R5") (pin "2") (pinfunction "2_2") (pintype "passive"))
    )
    (net (code "62") (name "Net-(IC3-IH)") (class "Default")
      (node (ref "D2") (pin "C") (pinfunction "C_C") (pintype "passive"))
      (node (ref "IC3") (pin "8") (pinfunction "IH_8") (pintype "bidirectional"))
      (node (ref "R12") (pin "1") (pinfunction "1_1") (pintype "passive"))
    )
    (net (code "63") (name "Net-(IC3-OH)") (class "Default")
      (node (ref "IC3") (pin "1") (pinfunction "OH_1") (pintype "bidirectional"))
      (node (ref "L2") (pin "1") (pinfunction "1_1") (pintype "bidirectional"))
    )
    (net (code "64") (name "Net-(IC3-VL)") (class "Default")
      (node (ref "IC3") (pin "3") (pinfunction "VL_3") (pintype "bidirectional"))
      (node (ref "L4") (pin "2") (pinfunction "2_2") (pintype "bidirectional"))
    )
    (net (code "65") (name "Net-(IC4-AVCC)") (class "Default")
      (node (ref "C27") (pin "1") (pinfunction "1_1") (pintype "passive"))
      (node (ref "IC4") (pin "46") (pinfunction "AVCC_46") (pintype "power_in"))
      (node (ref "R15") (pin "1") (pinfunction "1_1") (pintype "passive"))
    )
    (net (code "66") (name "Net-(IC4-EEDATA)") (class "Default")
      (node (ref "IC4") (pin "2") (pinfunction "EEDATA_2") (pintype "input"))
      (node (ref "R16") (pin "2") (pinfunction "2_2") (pintype "passive"))
    )
    (net (code "67") (name "Net-(L3-Pad1)") (class "Default")
      (node (ref "L3") (pin "1") (pinfunction "1_1") (pintype "bidirectional"))
      (node (ref "R12") (pin "2") (pinfunction "2_2") (pintype "passive"))
    )
    (net (code "68") (name "PTT_X") (class "Default")
      (node (ref "C15") (pin "1") (pinfunction "1_1") (pintype "passive"))
      (node (ref "CN4") (pin "4") (pinfunction "4_4") (pintype "bidirectional"))
      (node (ref "R20") (pin "2") (pinfunction "2_2") (pintype "passive"))
    )
    (net (code "69") (name "PWR_X") (class "Default")
      (node (ref "C18") (pin "1") (pinfunction "1_1") (pintype "passive"))
      (node (ref "CN4") (pin "8") (pinfunction "8_8") (pintype "bidirectional"))
      (node (ref "R23") (pin "2") (pinfunction "2_2") (pintype "passive"))
    )
    (net (code "70") (name "USB_IN_GND") (class "Default")
      (node (ref "C1") (pin "2") (pinfunction "2_2") (pintype "passive"))
      (node (ref "C2") (pin "2") (pinfunction "2_2") (pintype "passive"))
      (node (ref "CN1") (pin "5") (pinfunction "GND_5") (pintype "power_in"))
      (node (ref "D1") (pin "2") (pinfunction "GND_2") (pintype "bidirectional"))
      (node (ref "IC1") (pin "2") (pinfunction "GND1_2_2") (pintype "passive"))
      (node (ref "IC1") (pin "8") (pinfunction "GND1_8") (pintype "passive"))
      (node (ref "L7") (pin "1") (pinfunction "1_1") (pintype "bidirectional"))
    )
    (net (code "71") (name "VCC") (class "Default")
      (node (ref "C1") (pin "1") (pinfunction "1_1") (pintype "passive"))
      (node (ref "CN1") (pin "1") (pinfunction "VBUS_1") (pintype "power_in"))
      (node (ref "D1") (pin "5") (pinfunction "V+_5") (pintype "bidirectional"))
      (node (ref "IC1") (pin "1") (pinfunction "VBUS1_1") (pintype "power_in"))
    )
    (net (code "72") (name "VDD") (class "Default")
      (node (ref "C26") (pin "1") (pinfunction "1_1") (pintype "passive"))
      (node (ref "IC4") (pin "6") (pinfunction "3V3OUT_6") (pintype "power_in"))
      (node (ref "R14") (pin "1") (pinfunction "1_1") (pintype "passive"))
    )
    (net (code "73") (name "WK_232_TO_PIC") (class "Default")
      (node (ref "IC4") (pin "40") (pinfunction "BDBUS0_40") (pintype "bidirectional"))
    )
    (net (code "74") (name "WK_PIC_TO_232") (class "Default")
      (node (ref "IC4") (pin "39") (pinfunction "BDBUS1_39") (pintype "bidirectional"))
    )
    (net (code "75") (name "unconnected-(CN1-ID-Pad4)") (class "Default")
      (node (ref "CN1") (pin "4") (pinfunction "ID_4") (pintype "bidirectional"))
    )
    (net (code "76") (name "unconnected-(CN3-Pad1)") (class "Default")
      (node (ref "CN3") (pin "1") (pinfunction "1_1") (pintype "bidirectional"))
    )
    (net (code "77") (name "unconnected-(CN3-Pad4)") (class "Default")
      (node (ref "CN3") (pin "4") (pinfunction "4_4") (pintype "bidirectional"))
    )
    (net (code "78") (name "unconnected-(CN3-Pad6)") (class "Default")
      (node (ref "CN3") (pin "6") (pinfunction "6_6") (pintype "bidirectional"))
    )
    (net (code "79") (name "unconnected-(CN3-Pad7)") (class "Default")
      (node (ref "CN3") (pin "7") (pinfunction "7_7") (pintype "bidirectional"))
    )
    (net (code "80") (name "unconnected-(CN3-Pad8)") (class "Default")
      (node (ref "CN3") (pin "8") (pinfunction "8_8") (pintype "bidirectional"))
    )
    (net (code "81") (name "unconnected-(CN3-Pad9)") (class "Default")
      (node (ref "CN3") (pin "9") (pinfunction "9_9") (pintype "bidirectional"))
    )
    (net (code "82") (name "unconnected-(IC2-DM1-Pad11)") (class "Default")
      (node (ref "IC2") (pin "11") (pinfunction "DM1_11") (pintype "bidirectional"))
    )
    (net (code "83") (name "unconnected-(IC2-DM3-Pad19)") (class "Default")
      (node (ref "IC2") (pin "19") (pinfunction "DM3_19") (pintype "bidirectional"))
    )
    (net (code "84") (name "unconnected-(IC2-DP1-Pad12)") (class "Default")
      (node (ref "IC2") (pin "12") (pinfunction "DP1_12") (pintype "bidirectional"))
    )
    (net (code "85") (name "unconnected-(IC2-DP3-Pad20)") (class "Default")
      (node (ref "IC2") (pin "20") (pinfunction "DP3_20") (pintype "bidirectional"))
    )
    (net (code "86") (name "unconnected-(IC2-EECLK-Pad5)") (class "Default")
      (node (ref "IC2") (pin "5") (pinfunction "EECLK_5") (pintype "output"))
    )
    (net (code "87") (name "unconnected-(IC2-SUSPND-Pad32)") (class "Default")
      (node (ref "IC2") (pin "32") (pinfunction "SUSPND_32") (pintype "output"))
    )
    (net (code "88") (name "unconnected-(IC2-XTAL2-Pad29)") (class "Default")
      (node (ref "IC2") (pin "29") (pinfunction "XTAL2_29") (pintype "output"))
    )
    (net (code "89") (name "unconnected-(IC2-~{OVRCUR1}-Pad10)") (class "Default")
      (node (ref "IC2") (pin "10") (pinfunction "~{OVRCUR1}_10") (pintype "input"))
    )
    (net (code "90") (name "unconnected-(IC2-~{OVRCUR2}-Pad14)") (class "Default")
      (node (ref "IC2") (pin "14") (pinfunction "~{OVRCUR2}_14") (pintype "input"))
    )
    (net (code "91") (name "unconnected-(IC2-~{OVRCUR3}-Pad18)") (class "Default")
      (node (ref "IC2") (pin "18") (pinfunction "~{OVRCUR3}_18") (pintype "input"))
    )
    (net (code "92") (name "unconnected-(IC2-~{OVRCUR4}-Pad22)") (class "Default")
      (node (ref "IC2") (pin "22") (pinfunction "~{OVRCUR4}_22") (pintype "input"))
    )
    (net (code "93") (name "unconnected-(IC2-~{PWRON1}-Pad9)") (class "Default")
      (node (ref "IC2") (pin "9") (pinfunction "~{PWRON1}_9") (pintype "output"))
    )
    (net (code "94") (name "unconnected-(IC2-~{PWRON2}-Pad13)") (class "Default")
      (node (ref "IC2") (pin "13") (pinfunction "~{PWRON2}_13") (pintype "output"))
    )
    (net (code "95") (name "unconnected-(IC2-~{PWRON3}-Pad17)") (class "Default")
      (node (ref "IC2") (pin "17") (pinfunction "~{PWRON3}_17") (pintype "output"))
    )
    (net (code "96") (name "unconnected-(IC2-~{PWRON4}-Pad21)") (class "Default")
      (node (ref "IC2") (pin "21") (pinfunction "~{PWRON4}_21") (pintype "output"))
    )
    (net (code "97") (name "unconnected-(IC3-EN-Pad6)") (class "Default")
      (node (ref "IC3") (pin "6") (pinfunction "EN_6") (pintype "bidirectional"))
    )
    (net (code "98") (name "unconnected-(IC3-IL-Pad4)") (class "Default")
      (node (ref "IC3") (pin "4") (pinfunction "IL_4") (pintype "bidirectional"))
    )
    (net (code "99") (name "unconnected-(IC3-OL-Pad5)") (class "Default")
      (node (ref "IC3") (pin "5") (pinfunction "OL_5") (pintype "bidirectional"))
    )
    (net (code "100") (name "unconnected-(IC4--PWREN-Pad41)") (class "Default")
      (node (ref "IC4") (pin "41") (pinfunction "-PWREN_41") (pintype "output"))
    )
    (net (code "101") (name "unconnected-(IC4--RESETOUT-Pad5)") (class "Default")
      (node (ref "IC4") (pin "5") (pinfunction "-RESETOUT_5") (pintype "output"))
    )
    (net (code "102") (name "unconnected-(IC4-ACBUS0-Pad15)") (class "Default")
      (node (ref "IC4") (pin "15") (pinfunction "ACBUS0_15") (pintype "bidirectional"))
    )
    (net (code "103") (name "unconnected-(IC4-ACBUS1-Pad13)") (class "Default")
      (node (ref "IC4") (pin "13") (pinfunction "ACBUS1_13") (pintype "bidirectional"))
    )
    (net (code "104") (name "unconnected-(IC4-ACBUS2-Pad12)") (class "Default")
      (node (ref "IC4") (pin "12") (pinfunction "ACBUS2_12") (pintype "bidirectional"))
    )
    (net (code "105") (name "unconnected-(IC4-ACBUS3-Pad11)") (class "Default")
      (node (ref "IC4") (pin "11") (pinfunction "ACBUS3_11") (pintype "bidirectional"))
    )
    (net (code "106") (name "unconnected-(IC4-ADBUS2-Pad22)") (class "Default")
      (node (ref "IC4") (pin "22") (pinfunction "ADBUS2_22") (pintype "bidirectional"))
    )
    (net (code "107") (name "unconnected-(IC4-ADBUS3-Pad21)") (class "Default")
      (node (ref "IC4") (pin "21") (pinfunction "ADBUS3_21") (pintype "bidirectional"))
    )
    (net (code "108") (name "unconnected-(IC4-ADBUS4-Pad20)") (class "Default")
      (node (ref "IC4") (pin "20") (pinfunction "ADBUS4_20") (pintype "bidirectional"))
    )
    (net (code "109") (name "unconnected-(IC4-ADBUS5-Pad19)") (class "Default")
      (node (ref "IC4") (pin "19") (pinfunction "ADBUS5_19") (pintype "bidirectional"))
    )
    (net (code "110") (name "unconnected-(IC4-ADBUS6-Pad17)") (class "Default")
      (node (ref "IC4") (pin "17") (pinfunction "ADBUS6_17") (pintype "bidirectional"))
    )
    (net (code "111") (name "unconnected-(IC4-ADBUS7-Pad16)") (class "Default")
      (node (ref "IC4") (pin "16") (pinfunction "ADBUS7_16") (pintype "bidirectional"))
    )
    (net (code "112") (name "unconnected-(IC4-BCBUS0-Pad30)") (class "Default")
      (node (ref "IC4") (pin "30") (pinfunction "BCBUS0_30") (pintype "bidirectional"))
    )
    (net (code "113") (name "unconnected-(IC4-BCBUS1-Pad29)") (class "Default")
      (node (ref "IC4") (pin "29") (pinfunction "BCBUS1_29") (pintype "bidirectional"))
    )
    (net (code "114") (name "unconnected-(IC4-BCBUS2-Pad28)") (class "Default")
      (node (ref "IC4") (pin "28") (pinfunction "BCBUS2_28") (pintype "bidirectional"))
    )
    (net (code "115") (name "unconnected-(IC4-BCBUS3-Pad27)") (class "Default")
      (node (ref "IC4") (pin "27") (pinfunction "BCBUS3_27") (pintype "bidirectional"))
    )
    (net (code "116") (name "unconnected-(IC4-BDBUS2-Pad38)") (class "Default")
      (node (ref "IC4") (pin "38") (pinfunction "BDBUS2_38") (pintype "bidirectional"))
    )
    (net (code "117") (name "unconnected-(IC4-BDBUS3-Pad37)") (class "Default")
      (node (ref "IC4") (pin "37") (pinfunction "BDBUS3_37") (pintype "bidirectional"))
    )
    (net (code "118") (name "unconnected-(IC4-BDBUS4-Pad36)") (class "Default")
      (node (ref "IC4") (pin "36") (pinfunction "BDBUS4_36") (pintype "bidirectional"))
    )
    (net (code "119") (name "unconnected-(IC4-BDBUS5-Pad35)") (class "Default")
      (node (ref "IC4") (pin "35") (pinfunction "BDBUS5_35") (pintype "bidirectional"))
    )
    (net (code "120") (name "unconnected-(IC4-BDBUS6-Pad33)") (class "Default")
      (node (ref "IC4") (pin "33") (pinfunction "BDBUS6_33") (pintype "bidirectional"))
    )
    (net (code "121") (name "unconnected-(IC4-BDBUS7-Pad32)") (class "Default")
      (node (ref "IC4") (pin "32") (pinfunction "BDBUS7_32") (pintype "bidirectional"))
    )
    (net (code "122") (name "unconnected-(IC4-EECS-Pad48)") (class "Default")
      (node (ref "IC4") (pin "48") (pinfunction "EECS_48") (pintype "output"))
    )
    (net (code "123") (name "unconnected-(IC4-EESK-Pad1)") (class "Default")
      (node (ref "IC4") (pin "1") (pinfunction "EESK_1") (pintype "output"))
    )
    (net (code "124") (name "unconnected-(IC4-XTOUT-Pad44)") (class "Default")
      (node (ref "IC4") (pin "44") (pinfunction "XTOUT_44") (pintype "output"))
    )
  )
)
